# Sheet1.net
KiCad netlist of a schematic drawn in Altium Designer
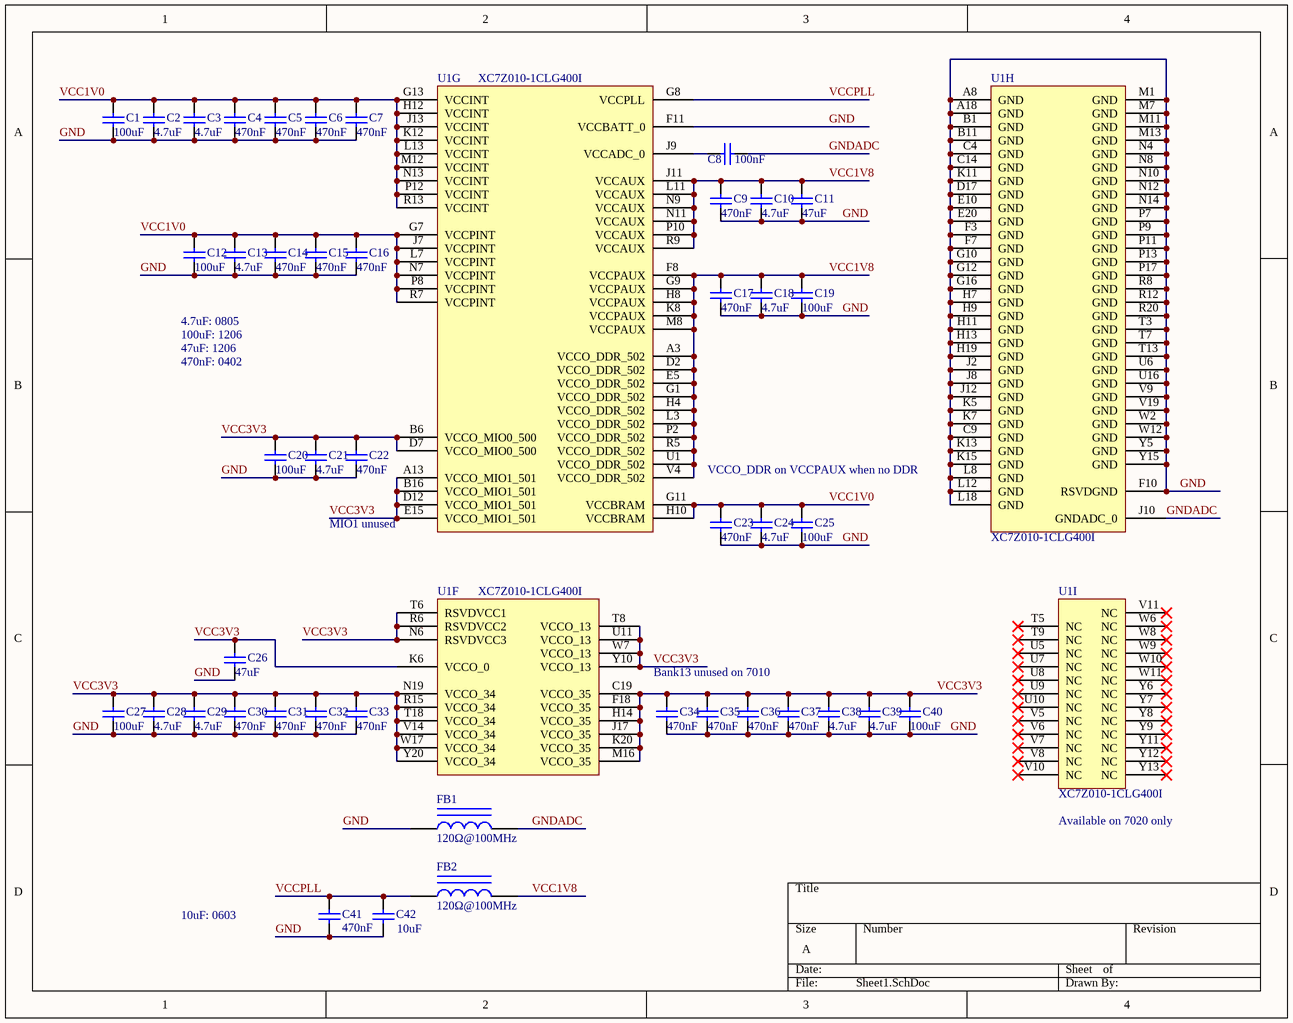
[diagram p0: Sheet1.SchDoc]

(export (version "E")
  (design (tool "Eeschema 10.0.6"))
  (components
    (comp (ref "C1")
      (value "100uF")
      (footprint "1206_C")
      (description "贴片电容")
      (libsource (lib "Cap") (part "1206 10uF (106) 10% 50V"))
    )
    (comp (ref "C2")
      (value "4.7uF")
      (footprint "0805_C")
      (description "贴片电容")
      (libsource (lib "Cap") (part "0805 4.7uF (475) 10% 25V"))
    )
    (comp (ref "C3")
      (value "4.7uF")
      (footprint "0805_C")
      (description "贴片电容")
      (libsource (lib "Cap") (part "0805 4.7uF (475) 10% 25V"))
    )
    (comp (ref "C4")
      (value "470nF")
      (footprint "0402_C")
      (description "贴片电容")
      (libsource (lib "Cap") (part "0402 470nF (474) 10% 10V"))
    )
    (comp (ref "C5")
      (value "470nF")
      (footprint "0402_C")
      (description "贴片电容")
      (libsource (lib "Cap") (part "0402 470nF (474) 10% 10V"))
    )
    (comp (ref "C6")
      (value "470nF")
      (footprint "0402_C")
      (description "贴片电容")
      (libsource (lib "Cap") (part "0402 470nF (474) 10% 10V"))
    )
    (comp (ref "C7")
      (value "470nF")
      (footprint "0402_C")
      (description "贴片电容")
      (libsource (lib "Cap") (part "0402 470nF (474) 10% 10V"))
    )
    (comp (ref "C8")
      (value "100nF")
      (footprint "1206_C")
      (description "贴片电容")
      (libsource (lib "Cap") (part "1206 100nF (104) 10% 50V"))
    )
    (comp (ref "C9")
      (value "470nF")
      (footprint "0402_C")
      (description "贴片电容")
      (libsource (lib "Cap") (part "0402 470nF (474) 10% 10V"))
    )
    (comp (ref "C10")
      (value "4.7uF")
      (footprint "0805_C")
      (description "贴片电容")
      (libsource (lib "Cap") (part "0805 4.7uF (475) 10% 25V"))
    )
    (comp (ref "C11")
      (value "47uF")
      (footprint "1206_C")
      (description "贴片电容")
      (libsource (lib "Cap") (part "1206 10uF (106) 10% 50V"))
    )
    (comp (ref "C12")
      (value "100uF")
      (footprint "1206_C")
      (description "贴片电容")
      (libsource (lib "Cap") (part "1206 10uF (106) 10% 50V"))
    )
    (comp (ref "C13")
      (value "4.7uF")
      (footprint "0805_C")
      (description "贴片电容")
      (libsource (lib "Cap") (part "0805 4.7uF (475) 10% 25V"))
    )
    (comp (ref "C14")
      (value "470nF")
      (footprint "0402_C")
      (description "贴片电容")
      (libsource (lib "Cap") (part "0402 470nF (474) 10% 10V"))
    )
    (comp (ref "C15")
      (value "470nF")
      (footprint "0402_C")
      (description "贴片电容")
      (libsource (lib "Cap") (part "0402 470nF (474) 10% 10V"))
    )
    (comp (ref "C16")
      (value "470nF")
      (footprint "0402_C")
      (description "贴片电容")
      (libsource (lib "Cap") (part "0402 470nF (474) 10% 10V"))
    )
    (comp (ref "C17")
      (value "470nF")
      (footprint "0402_C")
      (description "贴片电容")
      (libsource (lib "Cap") (part "0402 470nF (474) 10% 10V"))
    )
    (comp (ref "C18")
      (value "4.7uF")
      (footprint "0805_C")
      (description "贴片电容")
      (libsource (lib "Cap") (part "0805 4.7uF (475) 10% 25V"))
    )
    (comp (ref "C19")
      (value "100uF")
      (footprint "1206_C")
      (description "贴片电容")
      (libsource (lib "Cap") (part "1206 10uF (106) 10% 50V"))
    )
    (comp (ref "C20")
      (value "100uF")
      (footprint "1206_C")
      (description "贴片电容")
      (libsource (lib "Cap") (part "1206 10uF (106) 10% 50V"))
    )
    (comp (ref "C21")
      (value "4.7uF")
      (footprint "0805_C")
      (description "贴片电容")
      (libsource (lib "Cap") (part "0805 4.7uF (475) 10% 25V"))
    )
    (comp (ref "C22")
      (value "470nF")
      (footprint "0402_C")
      (description "贴片电容")
      (libsource (lib "Cap") (part "0402 470nF (474) 10% 10V"))
    )
    (comp (ref "C23")
      (value "470nF")
      (footprint "0402_C")
      (description "贴片电容")
      (libsource (lib "Cap") (part "0402 470nF (474) 10% 10V"))
    )
    (comp (ref "C24")
      (value "4.7uF")
      (footprint "0805_C")
      (description "贴片电容")
      (libsource (lib "Cap") (part "0805 4.7uF (475) 10% 25V"))
    )
    (comp (ref "C25")
      (value "100uF")
      (footprint "1206_C")
      (description "贴片电容")
      (libsource (lib "Cap") (part "1206 10uF (106) 10% 50V"))
    )
    (comp (ref "C26")
      (value "47uF")
      (footprint "1206_C")
      (description "贴片电容")
      (libsource (lib "Cap") (part "1206 10uF (106) 10% 50V"))
    )
    (comp (ref "C27")
      (value "100uF")
      (footprint "1206_C")
      (description "贴片电容")
      (libsource (lib "Cap") (part "1206 10uF (106) 10% 50V"))
    )
    (comp (ref "C28")
      (value "4.7uF")
      (footprint "0805_C")
      (description "贴片电容")
      (libsource (lib "Cap") (part "0805 4.7uF (475) 10% 25V"))
    )
    (comp (ref "C29")
      (value "4.7uF")
      (footprint "0805_C")
      (description "贴片电容")
      (libsource (lib "Cap") (part "0805 4.7uF (475) 10% 25V"))
    )
    (comp (ref "C30")
      (value "470nF")
      (footprint "0402_C")
      (description "贴片电容")
      (libsource (lib "Cap") (part "0402 470nF (474) 10% 10V"))
    )
    (comp (ref "C31")
      (value "470nF")
      (footprint "0402_C")
      (description "贴片电容")
      (libsource (lib "Cap") (part "0402 470nF (474) 10% 10V"))
    )
    (comp (ref "C32")
      (value "470nF")
      (footprint "0402_C")
      (description "贴片电容")
      (libsource (lib "Cap") (part "0402 470nF (474) 10% 10V"))
    )
    (comp (ref "C33")
      (value "470nF")
      (footprint "0402_C")
      (description "贴片电容")
      (libsource (lib "Cap") (part "0402 470nF (474) 10% 10V"))
    )
    (comp (ref "C34")
      (value "470nF")
      (footprint "0402_C")
      (description "贴片电容")
      (libsource (lib "Cap") (part "0402 470nF (474) 10% 10V"))
    )
    (comp (ref "C35")
      (value "470nF")
      (footprint "0402_C")
      (description "贴片电容")
      (libsource (lib "Cap") (part "0402 470nF (474) 10% 10V"))
    )
    (comp (ref "C36")
      (value "470nF")
      (footprint "0402_C")
      (description "贴片电容")
      (libsource (lib "Cap") (part "0402 470nF (474) 10% 10V"))
    )
    (comp (ref "C37")
      (value "470nF")
      (footprint "0402_C")
      (description "贴片电容")
      (libsource (lib "Cap") (part "0402 470nF (474) 10% 10V"))
    )
    (comp (ref "C38")
      (value "4.7uF")
      (footprint "0805_C")
      (description "贴片电容")
      (libsource (lib "Cap") (part "0805 4.7uF (475) 10% 25V"))
    )
    (comp (ref "C39")
      (value "4.7uF")
      (footprint "0805_C")
      (description "贴片电容")
      (libsource (lib "Cap") (part "0805 4.7uF (475) 10% 25V"))
    )
    (comp (ref "C40")
      (value "100uF")
      (footprint "1206_C")
      (description "贴片电容")
      (libsource (lib "Cap") (part "1206 10uF (106) 10% 50V"))
    )
    (comp (ref "C41")
      (value "470nF")
      (footprint "0402_C")
      (description "贴片电容")
      (libsource (lib "Cap") (part "0402 470nF (474) 10% 10V"))
    )
    (comp (ref "C42")
      (value "10uF")
      (footprint "0603_C")
      (description "贴片电容")
      (libsource (lib "Cap") (part "0603 10uF (106) 10% 10V"))
    )
    (comp (ref "FB1")
      (value "120Ω@100MHz")
      (footprint "0805_L")
      (description "贴片磁珠")
      (libsource (lib "IUD") (part "0805 600Ω 25% 100MHz"))
    )
    (comp (ref "FB2")
      (value "120Ω@100MHz")
      (footprint "0805_L")
      (description "贴片磁珠")
      (libsource (lib "IUD") (part "0805 600Ω 25% 100MHz"))
    )
    (comp (ref "U1")
      (value "XC7Z010-1CLG400I")
      (footprint "CLG400")
      (fields (field (name "GENERIC PART NUMBER") "XC7Z010") (field (name "MANUFACTURER") "Xilinx"))
      (libsource (lib "Xilinx Zynq-7000") (part "XC7Z010-1CLG400I"))
    )
  )
  (nets
    (net (code "1") (name "/GND") (class "Default")
      (node (ref "C1") (pin "2") (pinfunction "2_2") (pintype "passive"))
      (node (ref "C10") (pin "1") (pinfunction "1_1") (pintype "passive"))
      (node (ref "C11") (pin "1") (pinfunction "1_1") (pintype "passive"))
      (node (ref "C12") (pin "2") (pinfunction "2_2") (pintype "passive"))
      (node (ref "C13") (pin "2") (pinfunction "2_2") (pintype "passive"))
      (node (ref "C14") (pin "2") (pinfunction "2_2") (pintype "passive"))
      (node (ref "C15") (pin "2") (pinfunction "2_2") (pintype "passive"))
      (node (ref "C16") (pin "2") (pinfunction "2_2") (pintype "passive"))
      (node (ref "C17") (pin "1") (pinfunction "1_1") (pintype "passive"))
      (node (ref "C18") (pin "1") (pinfunction "1_1") (pintype "passive"))
      (node (ref "C19") (pin "1") (pinfunction "1_1") (pintype "passive"))
      (node (ref "C2") (pin "2") (pinfunction "2_2") (pintype "passive"))
      (node (ref "C20") (pin "2") (pinfunction "2_2") (pintype "passive"))
      (node (ref "C21") (pin "2") (pinfunction "2_2") (pintype "passive"))
      (node (ref "C22") (pin "2") (pinfunction "2_2") (pintype "passive"))
      (node (ref "C23") (pin "1") (pinfunction "1_1") (pintype "passive"))
      (node (ref "C24") (pin "1") (pinfunction "1_1") (pintype "passive"))
      (node (ref "C25") (pin "1") (pinfunction "1_1") (pintype "passive"))
      (node (ref "C26") (pin "1") (pinfunction "1_1") (pintype "passive"))
      (node (ref "C27") (pin "2") (pinfunction "2_2") (pintype "passive"))
      (node (ref "C28") (pin "2") (pinfunction "2_2") (pintype "passive"))
      (node (ref "C29") (pin "2") (pinfunction "2_2") (pintype "passive"))
      (node (ref "C3") (pin "2") (pinfunction "2_2") (pintype "passive"))
      (node (ref "C30") (pin "2") (pinfunction "2_2") (pintype "passive"))
      (node (ref "C31") (pin "2") (pinfunction "2_2") (pintype "passive"))
      (node (ref "C32") (pin "2") (pinfunction "2_2") (pintype "passive"))
      (node (ref "C33") (pin "2") (pinfunction "2_2") (pintype "passive"))
      (node (ref "C34") (pin "2") (pinfunction "2_2") (pintype "passive"))
      (node (ref "C35") (pin "2") (pinfunction "2_2") (pintype "passive"))
      (node (ref "C36") (pin "2") (pinfunction "2_2") (pintype "passive"))
      (node (ref "C37") (pin "2") (pinfunction "2_2") (pintype "passive"))
      (node (ref "C38") (pin "2") (pinfunction "2_2") (pintype "passive"))
      (node (ref "C39") (pin "2") (pinfunction "2_2") (pintype "passive"))
      (node (ref "C4") (pin "2") (pinfunction "2_2") (pintype "passive"))
      (node (ref "C40") (pin "2") (pinfunction "2_2") (pintype "passive"))
      (node (ref "C41") (pin "1") (pinfunction "1_1") (pintype "passive"))
      (node (ref "C42") (pin "1") (pinfunction "1_1") (pintype "passive"))
      (node (ref "C5") (pin "2") (pinfunction "2_2") (pintype "passive"))
      (node (ref "C6") (pin "2") (pinfunction "2_2") (pintype "passive"))
      (node (ref "C7") (pin "2") (pinfunction "2_2") (pintype "passive"))
      (node (ref "C9") (pin "1") (pinfunction "1_1") (pintype "passive"))
      (node (ref "FB1") (pin "1") (pinfunction "1_1") (pintype "passive"))
      (node (ref "U1") (pin "A18") (pinfunction "GND_A18") (pintype "power_in"))
      (node (ref "U1") (pin "A8") (pinfunction "GND_A8") (pintype "power_in"))
      (node (ref "U1") (pin "B1") (pinfunction "GND_B1") (pintype "power_in"))
      (node (ref "U1") (pin "B11") (pinfunction "GND_B11") (pintype "power_in"))
      (node (ref "U1") (pin "C14") (pinfunction "GND_C14") (pintype "power_in"))
      (node (ref "U1") (pin "C4") (pinfunction "GND_C4") (pintype "power_in"))
      (node (ref "U1") (pin "C9") (pinfunction "GND_C9") (pintype "power_in"))
      (node (ref "U1") (pin "D17") (pinfunction "GND_D17") (pintype "power_in"))
      (node (ref "U1") (pin "E10") (pinfunction "GND_E10") (pintype "power_in"))
      (node (ref "U1") (pin "E20") (pinfunction "GND_E20") (pintype "power_in"))
      (node (ref "U1") (pin "F10") (pinfunction "RSVDGND_F10") (pintype "power_in"))
      (node (ref "U1") (pin "F11") (pinfunction "VCCBATT_0_F11") (pintype "power_in"))
      (node (ref "U1") (pin "F3") (pinfunction "GND_F3") (pintype "power_in"))
      (node (ref "U1") (pin "F7") (pinfunction "GND_F7") (pintype "power_in"))
      (node (ref "U1") (pin "G10") (pinfunction "GND_G10") (pintype "power_in"))
      (node (ref "U1") (pin "G12") (pinfunction "GND_G12") (pintype "power_in"))
      (node (ref "U1") (pin "G16") (pinfunction "GND_G16") (pintype "power_in"))
      (node (ref "U1") (pin "H11") (pinfunction "GND_H11") (pintype "power_in"))
      (node (ref "U1") (pin "H13") (pinfunction "GND_H13") (pintype "power_in"))
      (node (ref "U1") (pin "H19") (pinfunction "GND_H19") (pintype "power_in"))
      (node (ref "U1") (pin "H7") (pinfunction "GND_H7") (pintype "power_in"))
      (node (ref "U1") (pin "H9") (pinfunction "GND_H9") (pintype "power_in"))
      (node (ref "U1") (pin "J12") (pinfunction "GND_J12") (pintype "power_in"))
      (node (ref "U1") (pin "J2") (pinfunction "GND_J2") (pintype "power_in"))
      (node (ref "U1") (pin "J8") (pinfunction "GND_J8") (pintype "power_in"))
      (node (ref "U1") (pin "K11") (pinfunction "GND_K11") (pintype "power_in"))
      (node (ref "U1") (pin "K13") (pinfunction "GND_K13") (pintype "power_in"))
      (node (ref "U1") (pin "K15") (pinfunction "GND_K15") (pintype "power_in"))
      (node (ref "U1") (pin "K5") (pinfunction "GND_K5") (pintype "power_in"))
      (node (ref "U1") (pin "K7") (pinfunction "GND_K7") (pintype "power_in"))
      (node (ref "U1") (pin "L12") (pinfunction "GND_L12") (pintype "power_in"))
      (node (ref "U1") (pin "L18") (pinfunction "GND_L18") (pintype "power_in"))
      (node (ref "U1") (pin "L8") (pinfunction "GND_L8") (pintype "power_in"))
      (node (ref "U1") (pin "M1") (pinfunction "GND_M1") (pintype "power_in"))
      (node (ref "U1") (pin "M11") (pinfunction "GND_M11") (pintype "power_in"))
      (node (ref "U1") (pin "M13") (pinfunction "GND_M13") (pintype "power_in"))
      (node (ref "U1") (pin "M7") (pinfunction "GND_M7") (pintype "power_in"))
      (node (ref "U1") (pin "N10") (pinfunction "GND_N10") (pintype "power_in"))
      (node (ref "U1") (pin "N12") (pinfunction "GND_N12") (pintype "power_in"))
      (node (ref "U1") (pin "N14") (pinfunction "GND_N14") (pintype "power_in"))
      (node (ref "U1") (pin "N4") (pinfunction "GND_N4") (pintype "power_in"))
      (node (ref "U1") (pin "N8") (pinfunction "GND_N8") (pintype "power_in"))
      (node (ref "U1") (pin "P11") (pinfunction "GND_P11") (pintype "power_in"))
      (node (ref "U1") (pin "P13") (pinfunction "GND_P13") (pintype "power_in"))
      (node (ref "U1") (pin "P17") (pinfunction "GND_P17") (pintype "power_in"))
      (node (ref "U1") (pin "P7") (pinfunction "GND_P7") (pintype "power_in"))
      (node (ref "U1") (pin "P9") (pinfunction "GND_P9") (pintype "power_in"))
      (node (ref "U1") (pin "R12") (pinfunction "GND_R12") (pintype "power_in"))
      (node (ref "U1") (pin "R20") (pinfunction "GND_R20") (pintype "power_in"))
      (node (ref "U1") (pin "R8") (pinfunction "GND_R8") (pintype "power_in"))
      (node (ref "U1") (pin "T13") (pinfunction "GND_T13") (pintype "power_in"))
      (node (ref "U1") (pin "T3") (pinfunction "GND_T3") (pintype "power_in"))
      (node (ref "U1") (pin "T7") (pinfunction "GND_T7") (pintype "power_in"))
      (node (ref "U1") (pin "U16") (pinfunction "GND_U16") (pintype "power_in"))
      (node (ref "U1") (pin "U6") (pinfunction "GND_U6") (pintype "power_in"))
      (node (ref "U1") (pin "V19") (pinfunction "GND_V19") (pintype "power_in"))
      (node (ref "U1") (pin "V9") (pinfunction "GND_V9") (pintype "power_in"))
      (node (ref "U1") (pin "W12") (pinfunction "GND_W12") (pintype "power_in"))
      (node (ref "U1") (pin "W2") (pinfunction "GND_W2") (pintype "power_in"))
      (node (ref "U1") (pin "Y15") (pinfunction "GND_Y15") (pintype "power_in"))
      (node (ref "U1") (pin "Y5") (pinfunction "GND_Y5") (pintype "power_in"))
    )
    (net (code "2") (name "/GNDADC") (class "Default")
      (node (ref "C8") (pin "2") (pinfunction "2_2") (pintype "passive"))
      (node (ref "FB1") (pin "2") (pinfunction "2_2") (pintype "passive"))
      (node (ref "U1") (pin "J10") (pinfunction "GNDADC_0_J10") (pintype "power_in"))
    )
    (net (code "3") (name "/VCC1V0") (class "Default")
      (node (ref "C1") (pin "1") (pinfunction "1_1") (pintype "passive"))
      (node (ref "C12") (pin "1") (pinfunction "1_1") (pintype "passive"))
      (node (ref "C13") (pin "1") (pinfunction "1_1") (pintype "passive"))
      (node (ref "C14") (pin "1") (pinfunction "1_1") (pintype "passive"))
      (node (ref "C15") (pin "1") (pinfunction "1_1") (pintype "passive"))
      (node (ref "C16") (pin "1") (pinfunction "1_1") (pintype "passive"))
      (node (ref "C2") (pin "1") (pinfunction "1_1") (pintype "passive"))
      (node (ref "C23") (pin "2") (pinfunction "2_2") (pintype "passive"))
      (node (ref "C24") (pin "2") (pinfunction "2_2") (pintype "passive"))
      (node (ref "C25") (pin "2") (pinfunction "2_2") (pintype "passive"))
      (node (ref "C3") (pin "1") (pinfunction "1_1") (pintype "passive"))
      (node (ref "C4") (pin "1") (pinfunction "1_1") (pintype "passive"))
      (node (ref "C5") (pin "1") (pinfunction "1_1") (pintype "passive"))
      (node (ref "C6") (pin "1") (pinfunction "1_1") (pintype "passive"))
      (node (ref "C7") (pin "1") (pinfunction "1_1") (pintype "passive"))
      (node (ref "U1") (pin "G11") (pinfunction "VCCBRAM_G11") (pintype "power_in"))
      (node (ref "U1") (pin "G13") (pinfunction "VCCINT_G13") (pintype "power_in"))
      (node (ref "U1") (pin "G7") (pinfunction "VCCPINT_G7") (pintype "power_in"))
      (node (ref "U1") (pin "H10") (pinfunction "VCCBRAM_H10") (pintype "power_in"))
      (node (ref "U1") (pin "H12") (pinfunction "VCCINT_H12") (pintype "power_in"))
      (node (ref "U1") (pin "J13") (pinfunction "VCCINT_J13") (pintype "power_in"))
      (node (ref "U1") (pin "J7") (pinfunction "VCCPINT_J7") (pintype "power_in"))
      (node (ref "U1") (pin "K12") (pinfunction "VCCINT_K12") (pintype "power_in"))
      (node (ref "U1") (pin "L13") (pinfunction "VCCINT_L13") (pintype "power_in"))
      (node (ref "U1") (pin "L7") (pinfunction "VCCPINT_L7") (pintype "power_in"))
      (node (ref "U1") (pin "M12") (pinfunction "VCCINT_M12") (pintype "power_in"))
      (node (ref "U1") (pin "N13") (pinfunction "VCCINT_N13") (pintype "power_in"))
      (node (ref "U1") (pin "N7") (pinfunction "VCCPINT_N7") (pintype "power_in"))
      (node (ref "U1") (pin "P12") (pinfunction "VCCINT_P12") (pintype "power_in"))
      (node (ref "U1") (pin "P8") (pinfunction "VCCPINT_P8") (pintype "power_in"))
      (node (ref "U1") (pin "R13") (pinfunction "VCCINT_R13") (pintype "power_in"))
      (node (ref "U1") (pin "R7") (pinfunction "VCCPINT_R7") (pintype "power_in"))
    )
    (net (code "4") (name "/VCC1V8") (class "Default")
      (node (ref "C10") (pin "2") (pinfunction "2_2") (pintype "passive"))
      (node (ref "C11") (pin "2") (pinfunction "2_2") (pintype "passive"))
      (node (ref "C17") (pin "2") (pinfunction "2_2") (pintype "passive"))
      (node (ref "C18") (pin "2") (pinfunction "2_2") (pintype "passive"))
      (node (ref "C19") (pin "2") (pinfunction "2_2") (pintype "passive"))
      (node (ref "C9") (pin "2") (pinfunction "2_2") (pintype "passive"))
      (node (ref "FB2") (pin "2") (pinfunction "2_2") (pintype "passive"))
      (node (ref "U1") (pin "A3") (pinfunction "VCCO_DDR_502_A3") (pintype "power_in"))
      (node (ref "U1") (pin "D2") (pinfunction "VCCO_DDR_502_D2") (pintype "power_in"))
      (node (ref "U1") (pin "E5") (pinfunction "VCCO_DDR_502_E5") (pintype "power_in"))
      (node (ref "U1") (pin "F8") (pinfunction "VCCPAUX_F8") (pintype "power_in"))
      (node (ref "U1") (pin "G1") (pinfunction "VCCO_DDR_502_G1") (pintype "power_in"))
      (node (ref "U1") (pin "G9") (pinfunction "VCCPAUX_G9") (pintype "power_in"))
      (node (ref "U1") (pin "H4") (pinfunction "VCCO_DDR_502_H4") (pintype "power_in"))
      (node (ref "U1") (pin "H8") (pinfunction "VCCPAUX_H8") (pintype "power_in"))
      (node (ref "U1") (pin "J11") (pinfunction "VCCAUX_J11") (pintype "power_in"))
      (node (ref "U1") (pin "K8") (pinfunction "VCCPAUX_K8") (pintype "power_in"))
      (node (ref "U1") (pin "L11") (pinfunction "VCCAUX_L11") (pintype "power_in"))
      (node (ref "U1") (pin "L3") (pinfunction "VCCO_DDR_502_L3") (pintype "power_in"))
      (node (ref "U1") (pin "M8") (pinfunction "VCCPAUX_M8") (pintype "power_in"))
      (node (ref "U1") (pin "N11") (pinfunction "VCCAUX_N11") (pintype "power_in"))
      (node (ref "U1") (pin "N9") (pinfunction "VCCAUX_N9") (pintype "power_in"))
      (node (ref "U1") (pin "P10") (pinfunction "VCCAUX_P10") (pintype "power_in"))
      (node (ref "U1") (pin "P2") (pinfunction "VCCO_DDR_502_P2") (pintype "power_in"))
      (node (ref "U1") (pin "R5") (pinfunction "VCCO_DDR_502_R5") (pintype "power_in"))
      (node (ref "U1") (pin "R9") (pinfunction "VCCAUX_R9") (pintype "power_in"))
      (node (ref "U1") (pin "U1") (pinfunction "VCCO_DDR_502_U1") (pintype "power_in"))
      (node (ref "U1") (pin "V4") (pinfunction "VCCO_DDR_502_V4") (pintype "power_in"))
    )
    (net (code "5") (name "/VCC3V3") (class "Default")
      (node (ref "C20") (pin "1") (pinfunction "1_1") (pintype "passive"))
      (node (ref "C21") (pin "1") (pinfunction "1_1") (pintype "passive"))
      (node (ref "C22") (pin "1") (pinfunction "1_1") (pintype "passive"))
      (node (ref "C26") (pin "2") (pinfunction "2_2") (pintype "passive"))
      (node (ref "C27") (pin "1") (pinfunction "1_1") (pintype "passive"))
      (node (ref "C28") (pin "1") (pinfunction "1_1") (pintype "passive"))
      (node (ref "C29") (pin "1") (pinfunction "1_1") (pintype "passive"))
      (node (ref "C30") (pin "1") (pinfunction "1_1") (pintype "passive"))
      (node (ref "C31") (pin "1") (pinfunction "1_1") (pintype "passive"))
      (node (ref "C32") (pin "1") (pinfunction "1_1") (pintype "passive"))
      (node (ref "C33") (pin "1") (pinfunction "1_1") (pintype "passive"))
      (node (ref "C34") (pin "1") (pinfunction "1_1") (pintype "passive"))
      (node (ref "C35") (pin "1") (pinfunction "1_1") (pintype "passive"))
      (node (ref "C36") (pin "1") (pinfunction "1_1") (pintype "passive"))
      (node (ref "C37") (pin "1") (pinfunction "1_1") (pintype "passive"))
      (node (ref "C38") (pin "1") (pinfunction "1_1") (pintype "passive"))
      (node (ref "C39") (pin "1") (pinfunction "1_1") (pintype "passive"))
      (node (ref "C40") (pin "1") (pinfunction "1_1") (pintype "passive"))
      (node (ref "U1") (pin "A13") (pinfunction "VCCO_MIO1_501_A13") (pintype "power_in"))
      (node (ref "U1") (pin "B16") (pinfunction "VCCO_MIO1_501_B16") (pintype "power_in"))
      (node (ref "U1") (pin "B6") (pinfunction "VCCO_MIO0_500_B6") (pintype "power_in"))
      (node (ref "U1") (pin "C19") (pinfunction "VCCO_35_C19") (pintype "power_in"))
      (node (ref "U1") (pin "D12") (pinfunction "VCCO_MIO1_501_D12") (pintype "power_in"))
      (node (ref "U1") (pin "D7") (pinfunction "VCCO_MIO0_500_D7") (pintype "power_in"))
      (node (ref "U1") (pin "E15") (pinfunction "VCCO_MIO1_501_E15") (pintype "power_in"))
      (node (ref "U1") (pin "F18") (pinfunction "VCCO_35_F18") (pintype "power_in"))
      (node (ref "U1") (pin "H14") (pinfunction "VCCO_35_H14") (pintype "power_in"))
      (node (ref "U1") (pin "J17") (pinfunction "VCCO_35_J17") (pintype "power_in"))
      (node (ref "U1") (pin "K20") (pinfunction "VCCO_35_K20") (pintype "power_in"))
      (node (ref "U1") (pin "K6") (pinfunction "VCCO_0_K6") (pintype "power_in"))
      (node (ref "U1") (pin "M16") (pinfunction "VCCO_35_M16") (pintype "power_in"))
      (node (ref "U1") (pin "N19") (pinfunction "VCCO_34_N19") (pintype "power_in"))
      (node (ref "U1") (pin "N6") (pinfunction "RSVDVCC3_N6") (pintype "power_in"))
      (node (ref "U1") (pin "R15") (pinfunction "VCCO_34_R15") (pintype "power_in"))
      (node (ref "U1") (pin "R6") (pinfunction "RSVDVCC2_R6") (pintype "power_in"))
      (node (ref "U1") (pin "T18") (pinfunction "VCCO_34_T18") (pintype "power_in"))
      (node (ref "U1") (pin "T6") (pinfunction "RSVDVCC1_T6") (pintype "power_in"))
      (node (ref "U1") (pin "T8") (pinfunction "VCCO_13_T8") (pintype "power_in"))
      (node (ref "U1") (pin "U11") (pinfunction "VCCO_13_U11") (pintype "power_in"))
      (node (ref "U1") (pin "V14") (pinfunction "VCCO_34_V14") (pintype "power_in"))
      (node (ref "U1") (pin "W17") (pinfunction "VCCO_34_W17") (pintype "power_in"))
      (node (ref "U1") (pin "W7") (pinfunction "VCCO_13_W7") (pintype "power_in"))
      (node (ref "U1") (pin "Y10") (pinfunction "VCCO_13_Y10") (pintype "power_in"))
      (node (ref "U1") (pin "Y20") (pinfunction "VCCO_34_Y20") (pintype "power_in"))
    )
    (net (code "6") (name "/VCCPLL") (class "Default")
      (node (ref "C41") (pin "2") (pinfunction "2_2") (pintype "passive"))
      (node (ref "C42") (pin "2") (pinfunction "2_2") (pintype "passive"))
      (node (ref "FB2") (pin "1") (pinfunction "1_1") (pintype "passive"))
      (node (ref "U1") (pin "G8") (pinfunction "VCCPLL_G8") (pintype "power_in"))
    )
    (net (code "7") (name "Net-(U1G-VCCADC_0)") (class "Default")
      (node (ref "C8") (pin "1") (pinfunction "1_1") (pintype "passive"))
      (node (ref "U1") (pin "J9") (pinfunction "VCCADC_0_J9") (pintype "power_in"))
    )
    (net (code "8") (name "unconnected-(U1I-NC-PadT5)") (class "Default")
      (node (ref "U1") (pin "T5") (pinfunction "NC_T5") (pintype "passive+no_connect"))
    )
    (net (code "9") (name "unconnected-(U1I-NC-PadT9)") (class "Default")
      (node (ref "U1") (pin "T9") (pinfunction "NC_T9") (pintype "passive+no_connect"))
    )
    (net (code "10") (name "unconnected-(U1I-NC-PadU5)") (class "Default")
      (node (ref "U1") (pin "U5") (pinfunction "NC_U5") (pintype "passive+no_connect"))
    )
    (net (code "11") (name "unconnected-(U1I-NC-PadU7)") (class "Default")
      (node (ref "U1") (pin "U7") (pinfunction "NC_U7") (pintype "passive+no_connect"))
    )
    (net (code "12") (name "unconnected-(U1I-NC-PadU8)") (class "Default")
      (node (ref "U1") (pin "U8") (pinfunction "NC_U8") (pintype "passive+no_connect"))
    )
    (net (code "13") (name "unconnected-(U1I-NC-PadU9)") (class "Default")
      (node (ref "U1") (pin "U9") (pinfunction "NC_U9") (pintype "passive+no_connect"))
    )
    (net (code "14") (name "unconnected-(U1I-NC-PadU10)") (class "Default")
      (node (ref "U1") (pin "U10") (pinfunction "NC_U10") (pintype "passive+no_connect"))
    )
    (net (code "15") (name "unconnected-(U1I-NC-PadV5)") (class "Default")
      (node (ref "U1") (pin "V5") (pinfunction "NC_V5") (pintype "passive+no_connect"))
    )
    (net (code "16") (name "unconnected-(U1I-NC-PadV6)") (class "Default")
      (node (ref "U1") (pin "V6") (pinfunction "NC_V6") (pintype "passive+no_connect"))
    )
    (net (code "17") (name "unconnected-(U1I-NC-PadV7)") (class "Default")
      (node (ref "U1") (pin "V7") (pinfunction "NC_V7") (pintype "passive+no_connect"))
    )
    (net (code "18") (name "unconnected-(U1I-NC-PadV8)") (class "Default")
      (node (ref "U1") (pin "V8") (pinfunction "NC_V8") (pintype "passive+no_connect"))
    )
    (net (code "19") (name "unconnected-(U1I-NC-PadV10)") (class "Default")
      (node (ref "U1") (pin "V10") (pinfunction "NC_V10") (pintype "passive+no_connect"))
    )
    (net (code "20") (name "unconnected-(U1I-NC-PadV11)") (class "Default")
      (node (ref "U1") (pin "V11") (pinfunction "NC_V11") (pintype "passive+no_connect"))
    )
    (net (code "21") (name "unconnected-(U1I-NC-PadW6)") (class "Default")
      (node (ref "U1") (pin "W6") (pinfunction "NC_W6") (pintype "passive+no_connect"))
    )
    (net (code "22") (name "unconnected-(U1I-NC-PadW8)") (class "Default")
      (node (ref "U1") (pin "W8") (pinfunction "NC_W8") (pintype "passive+no_connect"))
    )
    (net (code "23") (name "unconnected-(U1I-NC-PadW9)") (class "Default")
      (node (ref "U1") (pin "W9") (pinfunction "NC_W9") (pintype "passive+no_connect"))
    )
    (net (code "24") (name "unconnected-(U1I-NC-PadW10)") (class "Default")
      (node (ref "U1") (pin "W10") (pinfunction "NC_W10") (pintype "passive+no_connect"))
    )
    (net (code "25") (name "unconnected-(U1I-NC-PadW11)") (class "Default")
      (node (ref "U1") (pin "W11") (pinfunction "NC_W11") (pintype "passive+no_connect"))
    )
    (net (code "26") (name "unconnected-(U1I-NC-PadY6)") (class "Default")
      (node (ref "U1") (pin "Y6") (pinfunction "NC_Y6") (pintype "passive+no_connect"))
    )
    (net (code "27") (name "unconnected-(U1I-NC-PadY7)") (class "Default")
      (node (ref "U1") (pin "Y7") (pinfunction "NC_Y7") (pintype "passive+no_connect"))
    )
    (net (code "28") (name "unconnected-(U1I-NC-PadY8)") (class "Default")
      (node (ref "U1") (pin "Y8") (pinfunction "NC_Y8") (pintype "passive+no_connect"))
    )
    (net (code "29") (name "unconnected-(U1I-NC-PadY9)") (class "Default")
      (node (ref "U1") (pin "Y9") (pinfunction "NC_Y9") (pintype "passive+no_connect"))
    )
    (net (code "30") (name "unconnected-(U1I-NC-PadY11)") (class "Default")
      (node (ref "U1") (pin "Y11") (pinfunction "NC_Y11") (pintype "passive+no_connect"))
    )
    (net (code "31") (name "unconnected-(U1I-NC-PadY12)") (class "Default")
      (node (ref "U1") (pin "Y12") (pinfunction "NC_Y12") (pintype "passive+no_connect"))
    )
    (net (code "32") (name "unconnected-(U1I-NC-PadY13)") (class "Default")
      (node (ref "U1") (pin "Y13") (pinfunction "NC_Y13") (pintype "passive+no_connect"))
    )
  )
)
